# CONNECTIONS.net
KiCad netlist of a schematic drawn in Altium Designer
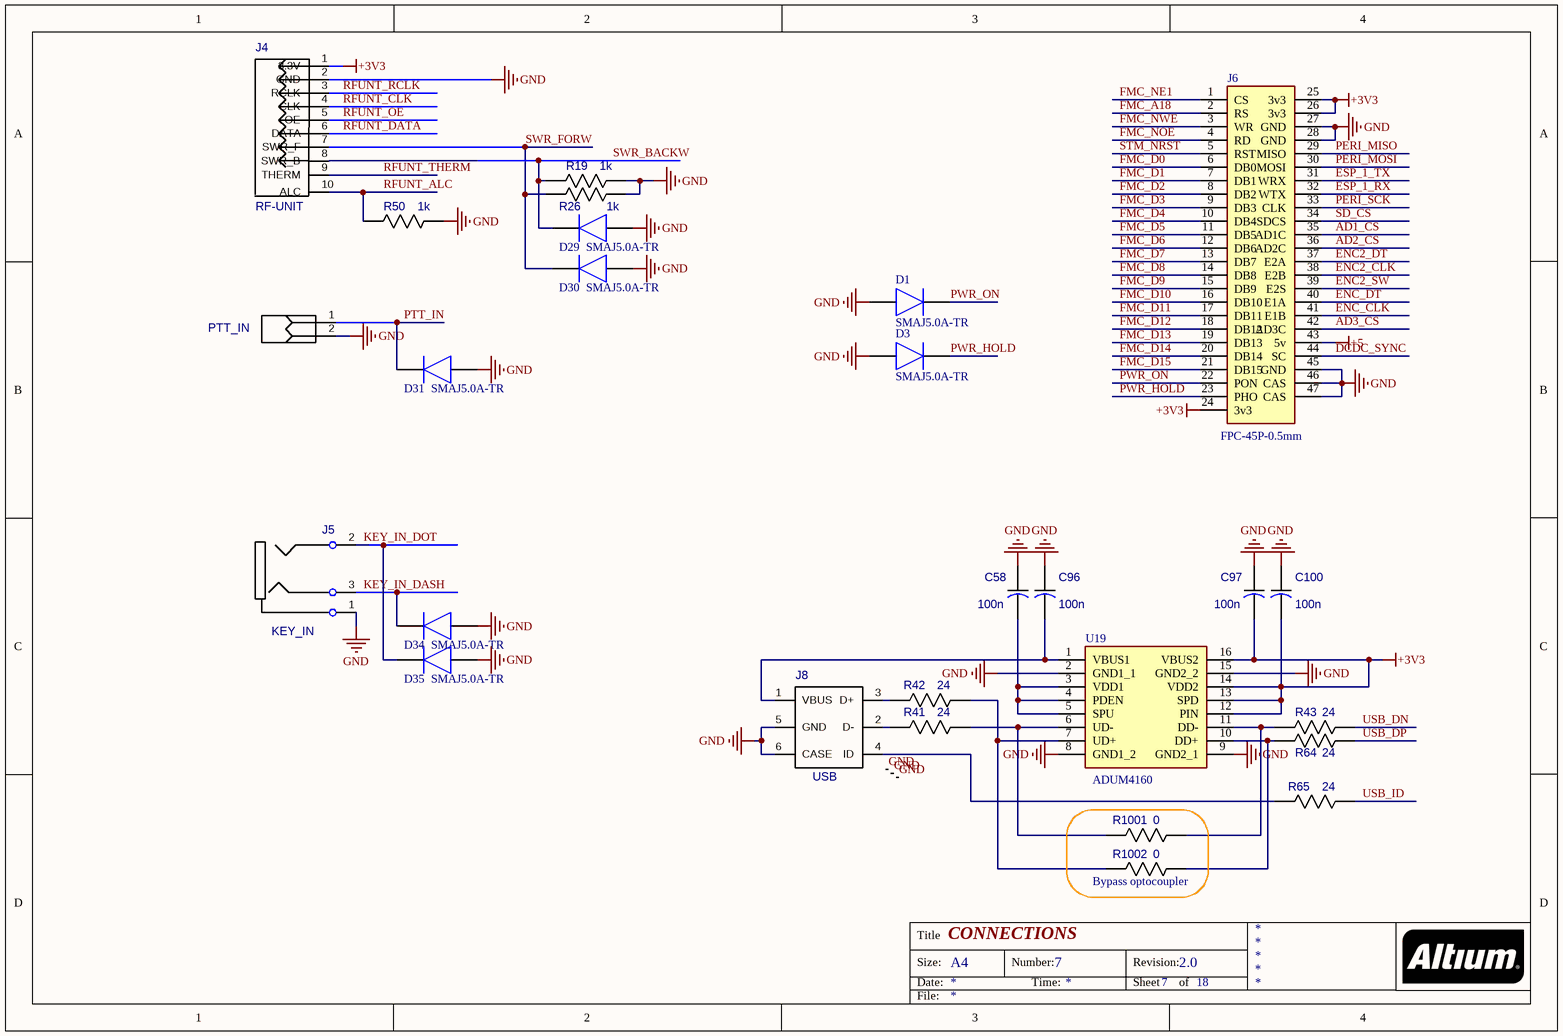
[diagram p0: CONNECTIONS.SchDoc]

(export (version "E")
  (design (tool "Eeschema 10.0.6"))
  (components
    (comp (ref "C58")
      (value "100n")
      (footprint "CAP_0805")
      (description "CAP_0805")
      (libsource (lib "*") (part "CAP_0805"))
    )
    (comp (ref "C96")
      (value "100n")
      (footprint "CAP_0805")
      (description "CAP_0805")
      (libsource (lib "*") (part "CAP_0805"))
    )
    (comp (ref "C97")
      (value "100n")
      (footprint "CAP_0805")
      (description "CAP_0805")
      (libsource (lib "*") (part "CAP_0805"))
    )
    (comp (ref "C100")
      (value "100n")
      (footprint "CAP_0805")
      (description "CAP_0805")
      (libsource (lib "*") (part "CAP_0805"))
    )
    (comp (ref "D1")
      (value "SMAJ5.0A-TR")
      (footprint "SMBJ36CATR")
      (description "Diode")
      (fields
        (field (name "MANUFACTURER_PART_NUMBER") "SMLVT3V3")
        (field (name "MOUSER PART NUMBER") "511-SMLVT3V3")
      )
      (libsource (lib "*") (part "SMLVT3V3"))
    )
    (comp (ref "D3")
      (value "SMAJ5.0A-TR")
      (footprint "SMBJ36CATR")
      (description "Diode")
      (fields
        (field (name "MANUFACTURER_PART_NUMBER") "SMLVT3V3")
        (field (name "MOUSER PART NUMBER") "511-SMLVT3V3")
      )
      (libsource (lib "*") (part "SMLVT3V3"))
    )
    (comp (ref "D29")
      (value "SMAJ5.0A-TR")
      (footprint "SamacSys:SMBJ36CATR")
      (description "Diode")
      (fields
        (field (name "MANUFACTURER_PART_NUMBER") "SMLVT3V3")
        (field (name "MOUSER PART NUMBER") "511-SMLVT3V3")
      )
      (libsource (lib "*") (part "SMLVT3V3"))
    )
    (comp (ref "D30")
      (value "SMAJ5.0A-TR")
      (footprint "SMBJ36CATR")
      (description "Diode")
      (fields
        (field (name "MANUFACTURER_PART_NUMBER") "SMLVT3V3")
        (field (name "MOUSER PART NUMBER") "511-SMLVT3V3")
      )
      (libsource (lib "*") (part "SMLVT3V3"))
    )
    (comp (ref "D31")
      (value "SMAJ5.0A-TR")
      (footprint "SamacSys:SMBJ36CATR")
      (description "Diode")
      (fields
        (field (name "MANUFACTURER_PART_NUMBER") "SMLVT3V3")
        (field (name "MOUSER PART NUMBER") "511-SMLVT3V3")
      )
      (libsource (lib "*") (part "SMLVT3V3"))
    )
    (comp (ref "D34")
      (value "SMAJ5.0A-TR")
      (footprint "SamacSys:SMBJ36CATR")
      (description "Diode")
      (fields
        (field (name "MANUFACTURER_PART_NUMBER") "SMLVT3V3")
        (field (name "MOUSER PART NUMBER") "511-SMLVT3V3")
      )
      (libsource (lib "*") (part "SMLVT3V3"))
    )
    (comp (ref "D35")
      (value "SMAJ5.0A-TR")
      (footprint "SamacSys:SMBJ36CATR")
      (description "Diode")
      (fields
        (field (name "MANUFACTURER_PART_NUMBER") "SMLVT3V3")
        (field (name "MOUSER PART NUMBER") "511-SMLVT3V3")
      )
      (libsource (lib "*") (part "SMLVT3V3"))
    )
    (comp (ref "J4")
      (value "RF-UNIT")
      (footprint "90131-0126")
      (description "2*5 Pin")
      (libsource (lib "MOTHERBOARD") (part "90131-0126"))
    )
    (comp (ref "J5")
      (value "KEY_IN")
      (footprint "SJ1-3525NG")
      (description "SJ1-3525NG")
      (libsource (lib "*") (part "SJ1-3523N"))
    )
    (comp (ref "J6")
      (value "FPC-45P-0.5mm")
      (footprint "MOTHERBOARD:FH12S45S05SH60")
      (description "Connector")
      (fields
        (field (name "MANUFACTURER_PART_NUMBER") "FH12S-45S-0.5SH(55)")
        (field (name "MOUSER PART NUMBER") "798-FH12S-45S-05SH55")
      )
      (libsource (lib "*") (part "FH12S-45S-0.5SH_55_"))
    )
    (comp (ref "J8")
      (value "USB")
      (footprint "2-1734035-3")
      (description "2-1734035-3")
      (libsource (lib "*") (part "2-1734035-3"))
    )
    (comp (ref "PTT_IN")
      (value "PTT_IN")
      (footprint "51022-0200")
      (description "51022-0200")
      (libsource (lib "*") (part "51022-0200"))
    )
    (comp (ref "R19")
      (value "1k")
      (footprint "RES_0805")
      (description "RES_0805")
      (libsource (lib "*") (part "RES_0805"))
    )
    (comp (ref "R26")
      (value "1k")
      (footprint "RES_0805")
      (description "RES_0805")
      (libsource (lib "*") (part "RES_0805"))
    )
    (comp (ref "R41")
      (value "24")
      (footprint "RES_0805")
      (description "RES_0805")
      (libsource (lib "*") (part "RES_0805"))
    )
    (comp (ref "R42")
      (value "24")
      (footprint "RES_0805")
      (description "RES_0805")
      (libsource (lib "*") (part "RES_0805"))
    )
    (comp (ref "R43")
      (value "24")
      (footprint "RES_0805")
      (description "RES_0805")
      (libsource (lib "*") (part "RES_0805"))
    )
    (comp (ref "R50")
      (value "1k")
      (footprint "RES_0805")
      (description "RES_0805")
      (libsource (lib "*") (part "RES_0805"))
    )
    (comp (ref "R64")
      (value "24")
      (footprint "RES_0805")
      (description "RES_0805")
      (libsource (lib "*") (part "RES_0805"))
    )
    (comp (ref "R65")
      (value "24")
      (footprint "RES_0805")
      (description "RES_0805")
      (libsource (lib "*") (part "RES_0805"))
    )
    (comp (ref "R1001")
      (value "0")
      (footprint "RES_0805")
      (description "RES_0805")
      (libsource (lib "*") (part "RES_0805"))
    )
    (comp (ref "R1002")
      (value "0")
      (footprint "RES_0805")
      (description "RES_0805")
      (libsource (lib "*") (part "RES_0805"))
    )
    (comp (ref "U19")
      (value "ADUM4160")
      (footprint "SOIC127P1032X265-16N")
      (description "Integrated Circuit")
      (fields
        (field (name "MANUFACTURER_PART_NUMBER") "ADUM4160BRWZ")
        (field (name "MOUSER PART NUMBER") "584-ADUM4160BRWZ")
      )
      (libsource (lib "*") (part "ADUM4160BRWZ"))
    )
  )
  (nets
    (net (code "1") (name "+3V3") (class "Default")
      (node (ref "C100") (pin "2") (pinfunction "2_2") (pintype "passive"))
      (node (ref "C97") (pin "2") (pinfunction "2_2") (pintype "passive"))
      (node (ref "J4") (pin "1") (pinfunction "3.3V_1") (pintype "passive"))
      (node (ref "J6") (pin "24") (pinfunction "3v3_24") (pintype "passive"))
      (node (ref "J6") (pin "25") (pinfunction "3v3_25") (pintype "passive"))
      (node (ref "J6") (pin "26") (pinfunction "3v3_26") (pintype "passive"))
      (node (ref "U19") (pin "12") (pinfunction "PIN_12") (pintype "passive"))
      (node (ref "U19") (pin "13") (pinfunction "SPD_13") (pintype "passive"))
      (node (ref "U19") (pin "14") (pinfunction "VDD2_14") (pintype "passive"))
      (node (ref "U19") (pin "16") (pinfunction "VBUS2_16") (pintype "passive"))
    )
    (net (code "2") (name "+5") (class "Default")
      (node (ref "J6") (pin "43") (pinfunction "5v_43") (pintype "passive"))
    )
    (net (code "3") (name "/AD1_CS") (class "Default")
      (node (ref "J6") (pin "35") (pinfunction "AD1C_35") (pintype "passive"))
    )
    (net (code "4") (name "/AD2_CS") (class "Default")
      (node (ref "J6") (pin "36") (pinfunction "AD2C_36") (pintype "passive"))
    )
    (net (code "5") (name "/AD3_CS") (class "Default")
      (node (ref "J6") (pin "42") (pinfunction "AD3C_42") (pintype "passive"))
    )
    (net (code "6") (name "/DCDC_SYNC") (class "Default")
      (node (ref "J6") (pin "44") (pinfunction "SC_44") (pintype "passive"))
    )
    (net (code "7") (name "/ENC2_CLK") (class "Default")
      (node (ref "J6") (pin "38") (pinfunction "E2B_38") (pintype "passive"))
    )
    (net (code "8") (name "/ENC2_DT") (class "Default")
      (node (ref "J6") (pin "37") (pinfunction "E2A_37") (pintype "passive"))
    )
    (net (code "9") (name "/ENC2_SW") (class "Default")
      (node (ref "J6") (pin "39") (pinfunction "E2S_39") (pintype "passive"))
    )
    (net (code "10") (name "/ENC_CLK") (class "Default")
      (node (ref "J6") (pin "41") (pinfunction "E1B_41") (pintype "passive"))
    )
    (net (code "11") (name "/ENC_DT") (class "Default")
      (node (ref "J6") (pin "40") (pinfunction "E1A_40") (pintype "passive"))
    )
    (net (code "12") (name "/ESP_1_RX") (class "Default")
      (node (ref "J6") (pin "32") (pinfunction "WTX_32") (pintype "passive"))
    )
    (net (code "13") (name "/ESP_1_TX") (class "Default")
      (node (ref "J6") (pin "31") (pinfunction "WRX_31") (pintype "passive"))
    )
    (net (code "14") (name "/FMC_A18") (class "Default")
      (node (ref "J6") (pin "2") (pinfunction "RS_2") (pintype "passive"))
    )
    (net (code "15") (name "/FMC_D0") (class "Default")
      (node (ref "J6") (pin "6") (pinfunction "DB0_6") (pintype "passive"))
    )
    (net (code "16") (name "/FMC_D1") (class "Default")
      (node (ref "J6") (pin "7") (pinfunction "DB1_7") (pintype "passive"))
    )
    (net (code "17") (name "/FMC_D2") (class "Default")
      (node (ref "J6") (pin "8") (pinfunction "DB2_8") (pintype "passive"))
    )
    (net (code "18") (name "/FMC_D3") (class "Default")
      (node (ref "J6") (pin "9") (pinfunction "DB3_9") (pintype "passive"))
    )
    (net (code "19") (name "/FMC_D4") (class "Default")
      (node (ref "J6") (pin "10") (pinfunction "DB4_10") (pintype "passive"))
    )
    (net (code "20") (name "/FMC_D5") (class "Default")
      (node (ref "J6") (pin "11") (pinfunction "DB5_11") (pintype "passive"))
    )
    (net (code "21") (name "/FMC_D6") (class "Default")
      (node (ref "J6") (pin "12") (pinfunction "DB6_12") (pintype "passive"))
    )
    (net (code "22") (name "/FMC_D7") (class "Default")
      (node (ref "J6") (pin "13") (pinfunction "DB7_13") (pintype "passive"))
    )
    (net (code "23") (name "/FMC_D8") (class "Default")
      (node (ref "J6") (pin "14") (pinfunction "DB8_14") (pintype "passive"))
    )
    (net (code "24") (name "/FMC_D9") (class "Default")
      (node (ref "J6") (pin "15") (pinfunction "DB9_15") (pintype "passive"))
    )
    (net (code "25") (name "/FMC_D10") (class "Default")
      (node (ref "J6") (pin "16") (pinfunction "DB10_16") (pintype "passive"))
    )
    (net (code "26") (name "/FMC_D11") (class "Default")
      (node (ref "J6") (pin "17") (pinfunction "DB11_17") (pintype "passive"))
    )
    (net (code "27") (name "/FMC_D12") (class "Default")
      (node (ref "J6") (pin "18") (pinfunction "DB12_18") (pintype "passive"))
    )
    (net (code "28") (name "/FMC_D13") (class "Default")
      (node (ref "J6") (pin "19") (pinfunction "DB13_19") (pintype "passive"))
    )
    (net (code "29") (name "/FMC_D14") (class "Default")
      (node (ref "J6") (pin "20") (pinfunction "DB14_20") (pintype "passive"))
    )
    (net (code "30") (name "/FMC_D15") (class "Default")
      (node (ref "J6") (pin "21") (pinfunction "DB15_21") (pintype "passive"))
    )
    (net (code "31") (name "/FMC_NE1") (class "Default")
      (node (ref "J6") (pin "1") (pinfunction "CS_1") (pintype "passive"))
    )
    (net (code "32") (name "/FMC_NOE") (class "Default")
      (node (ref "J6") (pin "4") (pinfunction "RD_4") (pintype "passive"))
    )
    (net (code "33") (name "/FMC_NWE") (class "Default")
      (node (ref "J6") (pin "3") (pinfunction "WR_3") (pintype "passive"))
    )
    (net (code "34") (name "/KEY_IN_DASH") (class "Default")
      (node (ref "D34") (pin "1") (pinfunction "K_1") (pintype "passive"))
      (node (ref "J5") (pin "3") (pinfunction "ring_3") (pintype "passive"))
    )
    (net (code "35") (name "/KEY_IN_DOT") (class "Default")
      (node (ref "D35") (pin "1") (pinfunction "K_1") (pintype "passive"))
      (node (ref "J5") (pin "2") (pinfunction "tip_2") (pintype "passive"))
    )
    (net (code "36") (name "/PERI_MISO") (class "Default")
      (node (ref "J6") (pin "29") (pinfunction "MISO_29") (pintype "passive"))
    )
    (net (code "37") (name "/PERI_MOSI") (class "Default")
      (node (ref "J6") (pin "30") (pinfunction "MOSI_30") (pintype "passive"))
    )
    (net (code "38") (name "/PERI_SCK") (class "Default")
      (node (ref "J6") (pin "33") (pinfunction "CLK_33") (pintype "passive"))
    )
    (net (code "39") (name "/PTT_IN") (class "Default")
      (node (ref "D31") (pin "1") (pinfunction "K_1") (pintype "passive"))
      (node (ref "PTT_IN") (pin "1") (pinfunction "1_1") (pintype "passive"))
    )
    (net (code "40") (name "/PWR_HOLD") (class "Default")
      (node (ref "D3") (pin "1") (pinfunction "K_1") (pintype "passive"))
      (node (ref "J6") (pin "23") (pinfunction "PHO_23") (pintype "passive"))
    )
    (net (code "41") (name "/PWR_ON") (class "Default")
      (node (ref "D1") (pin "1") (pinfunction "K_1") (pintype "passive"))
      (node (ref "J6") (pin "22") (pinfunction "PON_22") (pintype "passive"))
    )
    (net (code "42") (name "/RFUNT_ALC") (class "Default")
      (node (ref "J4") (pin "10") (pinfunction "ALC_10") (pintype "passive"))
      (node (ref "R50") (pin "1") (pinfunction "1_1") (pintype "passive"))
    )
    (net (code "43") (name "/RFUNT_CLK") (class "Default")
      (node (ref "J4") (pin "4") (pinfunction "CLK_4") (pintype "passive"))
    )
    (net (code "44") (name "/RFUNT_DATA") (class "Default")
      (node (ref "J4") (pin "6") (pinfunction "DATA_6") (pintype "passive"))
    )
    (net (code "45") (name "/RFUNT_OE") (class "Default")
      (node (ref "J4") (pin "5") (pinfunction "OE_5") (pintype "passive"))
    )
    (net (code "46") (name "/RFUNT_RCLK") (class "Default")
      (node (ref "J4") (pin "3") (pinfunction "RCLK_3") (pintype "passive"))
    )
    (net (code "47") (name "/RFUNT_THERM") (class "Default")
      (node (ref "J4") (pin "9") (pinfunction "THERM_9") (pintype "passive"))
    )
    (net (code "48") (name "/SD_CS") (class "Default")
      (node (ref "J6") (pin "34") (pinfunction "SDCS_34") (pintype "passive"))
    )
    (net (code "49") (name "/STM_NRST") (class "Default")
      (node (ref "J6") (pin "5") (pinfunction "RST_5") (pintype "passive"))
    )
    (net (code "50") (name "/SWR_BACKW") (class "Default")
      (node (ref "D29") (pin "1") (pinfunction "K_1") (pintype "passive"))
      (node (ref "J4") (pin "8") (pinfunction "SWR_B_8") (pintype "passive"))
      (node (ref "R19") (pin "1") (pinfunction "1_1") (pintype "passive"))
    )
    (net (code "51") (name "/SWR_FORW") (class "Default")
      (node (ref "D30") (pin "1") (pinfunction "K_1") (pintype "passive"))
      (node (ref "J4") (pin "7") (pinfunction "SWR_F_7") (pintype "passive"))
      (node (ref "R26") (pin "1") (pinfunction "1_1") (pintype "passive"))
    )
    (net (code "52") (name "/USB_DN") (class "Default")
      (node (ref "R43") (pin "2") (pinfunction "2_2") (pintype "passive"))
    )
    (net (code "53") (name "/USB_DP") (class "Default")
      (node (ref "R64") (pin "2") (pinfunction "2_2") (pintype "passive"))
    )
    (net (code "54") (name "/USB_ID") (class "Default")
      (node (ref "R65") (pin "2") (pinfunction "2_2") (pintype "passive"))
    )
    (net (code "55") (name "GND") (class "Default")
      (node (ref "C100") (pin "1") (pinfunction "1_1") (pintype "passive"))
      (node (ref "C58") (pin "1") (pinfunction "1_1") (pintype "passive"))
      (node (ref "C96") (pin "1") (pinfunction "1_1") (pintype "passive"))
      (node (ref "C97") (pin "1") (pinfunction "1_1") (pintype "passive"))
      (node (ref "D1") (pin "2") (pinfunction "A_2") (pintype "passive"))
      (node (ref "D29") (pin "2") (pinfunction "A_2") (pintype "passive"))
      (node (ref "D3") (pin "2") (pinfunction "A_2") (pintype "passive"))
      (node (ref "D30") (pin "2") (pinfunction "A_2") (pintype "passive"))
      (node (ref "D31") (pin "2") (pinfunction "A_2") (pintype "passive"))
      (node (ref "D34") (pin "2") (pinfunction "A_2") (pintype "passive"))
      (node (ref "D35") (pin "2") (pinfunction "A_2") (pintype "passive"))
      (node (ref "J4") (pin "2") (pinfunction "GND_2") (pintype "passive"))
      (node (ref "J5") (pin "1") (pinfunction "sleeve_1") (pintype "passive"))
      (node (ref "J6") (pin "27") (pinfunction "GND_27") (pintype "passive"))
      (node (ref "J6") (pin "28") (pinfunction "GND_28") (pintype "passive"))
      (node (ref "J6") (pin "45") (pinfunction "GND_45") (pintype "passive"))
      (node (ref "J6") (pin "46") (pinfunction "CAS_46") (pintype "passive"))
      (node (ref "J6") (pin "47") (pinfunction "CAS_47") (pintype "passive"))
      (node (ref "J8") (pin "5") (pinfunction "GND_5") (pintype "passive"))
      (node (ref "J8") (pin "6") (pinfunction "CASE_6") (pintype "passive"))
      (node (ref "J8") (pin "7") (pinfunction "0_7") (pintype "passive"))
      (node (ref "J8") (pin "8") (pinfunction "0_8") (pintype "passive"))
      (node (ref "J8") (pin "9") (pinfunction "0_9") (pintype "passive"))
      (node (ref "PTT_IN") (pin "2") (pinfunction "2_2") (pintype "passive"))
      (node (ref "R19") (pin "2") (pinfunction "2_2") (pintype "passive"))
      (node (ref "R26") (pin "2") (pinfunction "2_2") (pintype "passive"))
      (node (ref "R50") (pin "2") (pinfunction "2_2") (pintype "passive"))
      (node (ref "U19") (pin "15") (pinfunction "GND2_2_15") (pintype "passive"))
      (node (ref "U19") (pin "2") (pinfunction "GND1_1_2") (pintype "passive"))
      (node (ref "U19") (pin "8") (pinfunction "GND1_2_8") (pintype "passive"))
      (node (ref "U19") (pin "9") (pinfunction "GND2_1_9") (pintype "passive"))
    )
    (net (code "56") (name "Net-(J8-D+)") (class "Default")
      (node (ref "J8") (pin "3") (pinfunction "D+_3") (pintype "passive"))
      (node (ref "R42") (pin "1") (pinfunction "1_1") (pintype "passive"))
    )
    (net (code "57") (name "Net-(J8-D-)") (class "Default")
      (node (ref "J8") (pin "2") (pinfunction "D-_2") (pintype "passive"))
      (node (ref "R41") (pin "1") (pinfunction "1_1") (pintype "passive"))
    )
    (net (code "58") (name "Net-(J8-ID)") (class "Default")
      (node (ref "J8") (pin "4") (pinfunction "ID_4") (pintype "passive"))
      (node (ref "R65") (pin "1") (pinfunction "1_1") (pintype "passive"))
    )
    (net (code "59") (name "Net-(J8-VBUS)") (class "Default")
      (node (ref "C96") (pin "2") (pinfunction "2_2") (pintype "passive"))
      (node (ref "J8") (pin "1") (pinfunction "VBUS_1") (pintype "passive"))
      (node (ref "U19") (pin "1") (pinfunction "VBUS1_1") (pintype "passive"))
    )
    (net (code "60") (name "Net-(U19-DD+)") (class "Default")
      (node (ref "R1002") (pin "2") (pinfunction "2_2") (pintype "passive"))
      (node (ref "R64") (pin "1") (pinfunction "1_1") (pintype "passive"))
      (node (ref "U19") (pin "10") (pinfunction "DD+_10") (pintype "passive"))
    )
    (net (code "61") (name "Net-(U19-DD-)") (class "Default")
      (node (ref "R1001") (pin "2") (pinfunction "2_2") (pintype "passive"))
      (node (ref "R43") (pin "1") (pinfunction "1_1") (pintype "passive"))
      (node (ref "U19") (pin "11") (pinfunction "DD-_11") (pintype "passive"))
    )
    (net (code "62") (name "Net-(U19-PDEN)") (class "Default")
      (node (ref "C58") (pin "2") (pinfunction "2_2") (pintype "passive"))
      (node (ref "U19") (pin "3") (pinfunction "VDD1_3") (pintype "passive"))
      (node (ref "U19") (pin "4") (pinfunction "PDEN_4") (pintype "passive"))
      (node (ref "U19") (pin "5") (pinfunction "SPU_5") (pintype "passive"))
    )
    (net (code "63") (name "Net-(U19-UD+)") (class "Default")
      (node (ref "R1002") (pin "1") (pinfunction "1_1") (pintype "passive"))
      (node (ref "R42") (pin "2") (pinfunction "2_2") (pintype "passive"))
      (node (ref "U19") (pin "7") (pinfunction "UD+_7") (pintype "passive"))
    )
    (net (code "64") (name "Net-(U19-UD-)") (class "Default")
      (node (ref "R1001") (pin "1") (pinfunction "1_1") (pintype "passive"))
      (node (ref "R41") (pin "2") (pinfunction "2_2") (pintype "passive"))
      (node (ref "U19") (pin "6") (pinfunction "UD-_6") (pintype "passive"))
    )
  )
)
